# lt8471.net
KiCad netlist of a schematic drawn in EAGLE
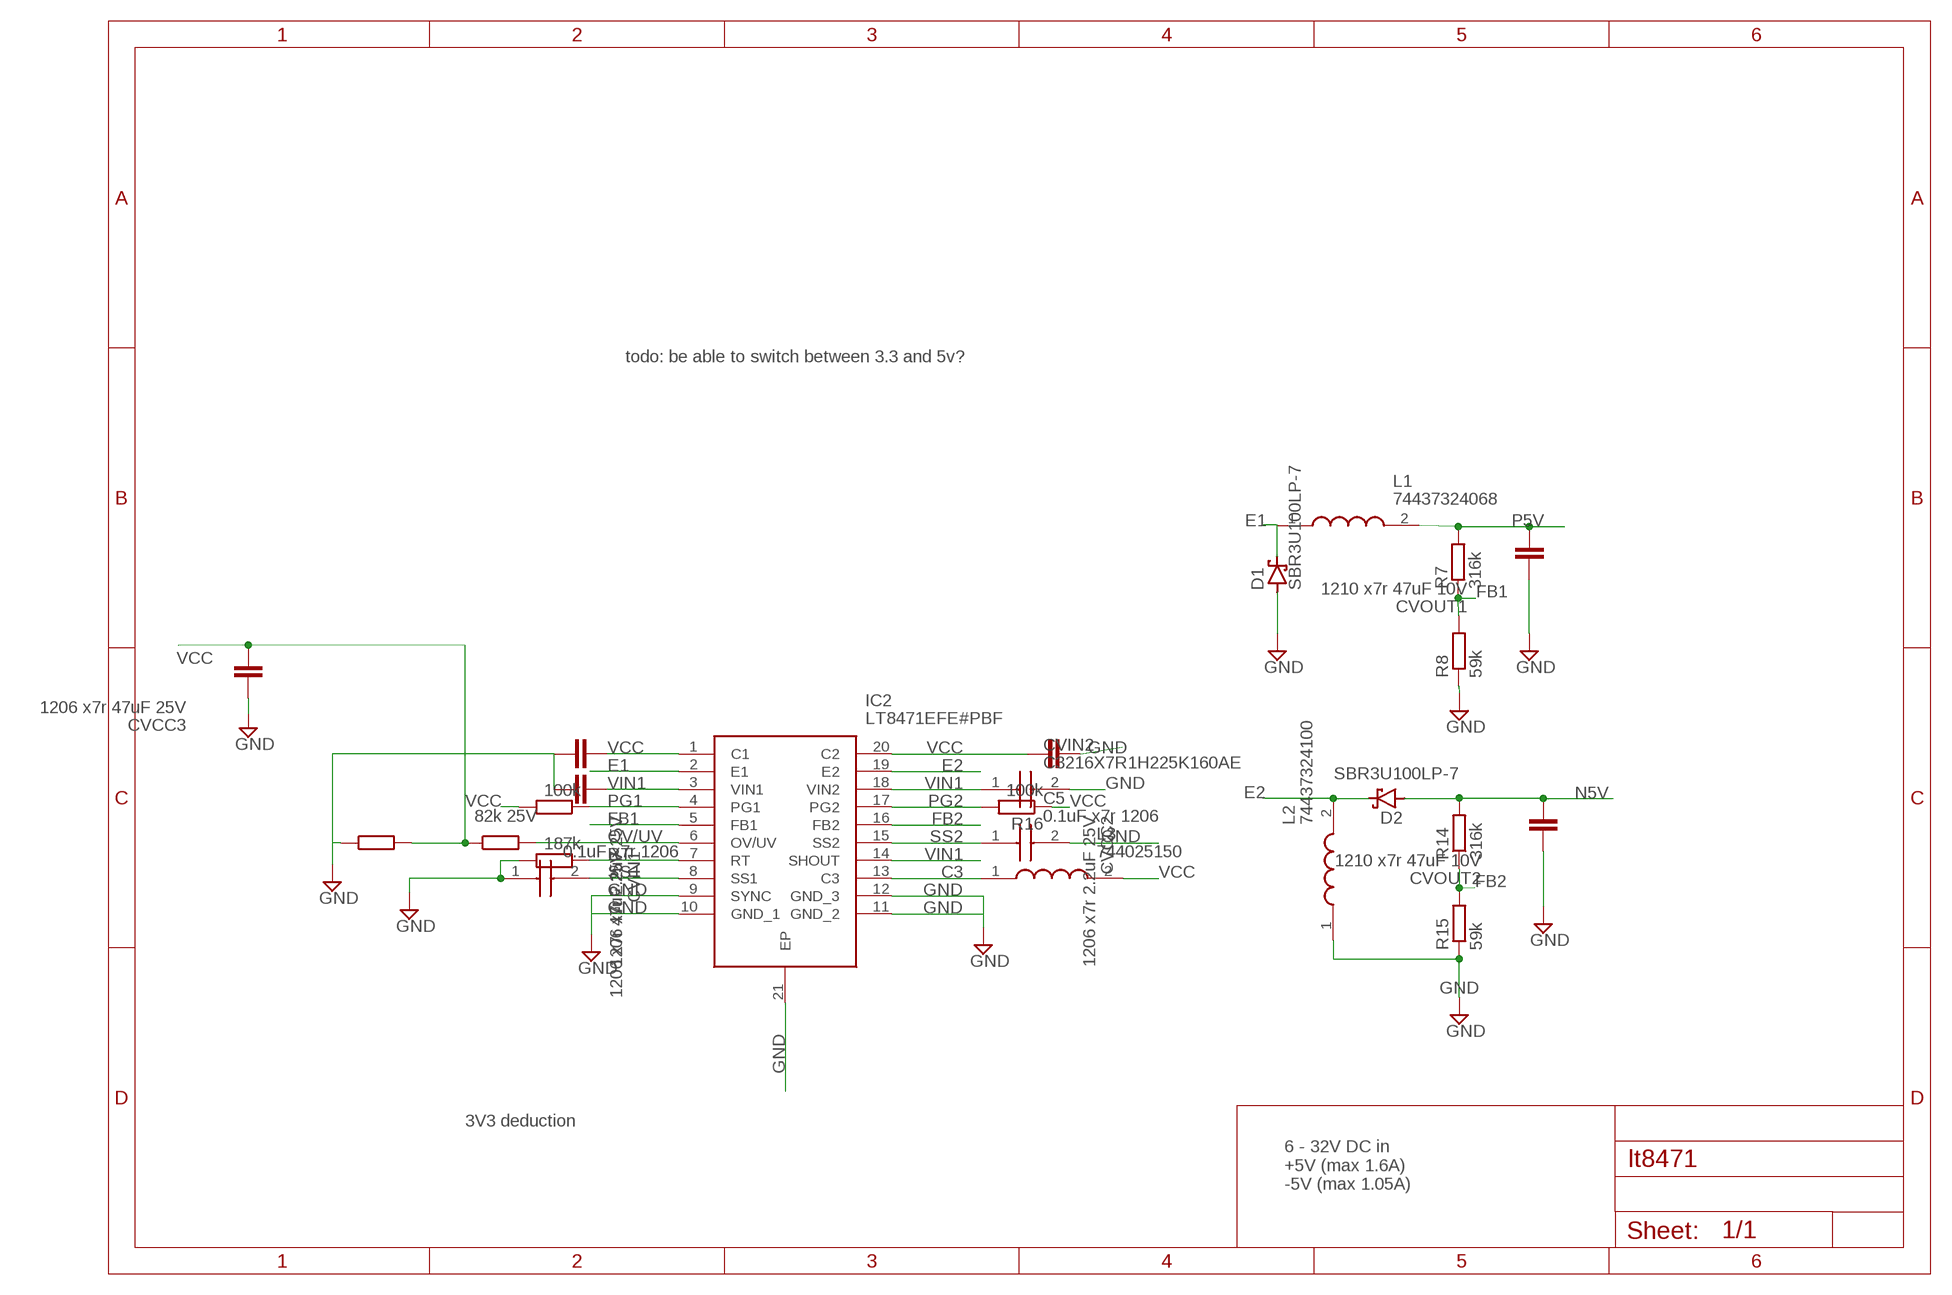
[diagram p0: schematic, sheet 1]

(export (version "E")
  (design (tool "Eeschema 10.0.6"))
  (components
    (comp (ref "C3")
      (value "0.1uF x7r 1206")
      (footprint "eagle-import:CAPC3416X90N")
      (fields (field (name "MANUFACTURER_PART_NUMBER") "MCSH31B104K500CT"))
      (libsource (lib "eagle-import") (part "MCSH31B104K500CT"))
    )
    (comp (ref "C5")
      (value "0.1uF x7r 1206")
      (footprint "eagle-import:CAPC3416X90N")
      (fields (field (name "MANUFACTURER_PART_NUMBER") "MCSH31B104K500CT"))
      (libsource (lib "eagle-import") (part "MCSH31B104K500CT"))
    )
    (comp (ref "CVCC1")
      (value "1206 x7r 2.2uF 25V")
      (footprint "eagle-import:C1206")
      (libsource (lib "eagle-import") (part "C-EUC1206"))
    )
    (comp (ref "CVCC2")
      (value "1206 x7r 2.2uF 25V")
      (footprint "eagle-import:C1206")
      (libsource (lib "eagle-import") (part "C-EUC1206"))
    )
    (comp (ref "CVCC3")
      (value "1206 x7r 47uF 25V")
      (footprint "eagle-import:C1210")
      (libsource (lib "eagle-import") (part "C-EUC1210"))
    )
    (comp (ref "CVIN1")
      (value "1206 x7r 47uF 25V")
      (footprint "eagle-import:C1210")
      (libsource (lib "eagle-import") (part "C-EUC1210"))
    )
    (comp (ref "CVIN2")
      (value "C3216X7R1H225K160AE")
      (footprint "eagle-import:CAPC3216X180N")
      (fields (field (name "MOUSER_PART_NUMBER") "810-C3216X7R1H225KST"))
      (libsource (lib "eagle-import") (part "C3216X7R1H225K160AE"))
    )
    (comp (ref "CVOUT1")
      (value "1210 x7r 47uF 10V")
      (footprint "eagle-import:C1210")
      (libsource (lib "eagle-import") (part "C-EUC1210"))
    )
    (comp (ref "CVOUT2")
      (value "1210 x7r 47uF 10V")
      (footprint "eagle-import:C1210")
      (libsource (lib "eagle-import") (part "C-EUC1210"))
    )
    (comp (ref "D1")
      (value "SBR3U100LP-7")
      (footprint "eagle-import:SBR3U100LP7")
      (fields
        (field (name "MOUSER_PART_NUMBER") "621-SBR3U100LP-7")
        (field (name "RS_PART_NUMBER") "8855599P")
      )
      (libsource (lib "eagle-import") (part "SBR3U100LP-7"))
    )
    (comp (ref "D2")
      (value "SBR3U100LP-7")
      (footprint "eagle-import:SBR3U100LP7")
      (fields
        (field (name "MOUSER_PART_NUMBER") "621-SBR3U100LP-7")
        (field (name "RS_PART_NUMBER") "8855599P")
      )
      (libsource (lib "eagle-import") (part "SBR3U100LP-7"))
    )
    (comp (ref "IC2")
      (value "LT8471EFE#PBF")
      (footprint "eagle-import:SOP65P640X120-21N")
      (fields
        (field (name "MOUSER_PART_NUMBER") "584-LT8471EFE#PBF")
        (field (name "RS_PART_NUMBER") "1513320")
      )
      (libsource (lib "eagle-import") (part "LT8471EFE#PBF"))
    )
    (comp (ref "L1")
      (value "74437324068")
      (footprint "eagle-import:WE-LHMI_402048")
      (fields
        (field (name "MOUSER_PART_NUMBER") "710-74437324068")
        (field (name "RS_PART_NUMBER") "7568480P")
      )
      (libsource (lib "eagle-import") (part "74437324068"))
    )
    (comp (ref "L2")
      (value "74437324100")
      (footprint "eagle-import:WE-LHMI_402048")
      (fields
        (field (name "MOUSER_PART_NUMBER") "710-74437324100")
        (field (name "RS_PART_NUMBER") "7568487P")
      )
      (libsource (lib "eagle-import") (part "74437324100"))
    )
    (comp (ref "L3")
      (value "744025150")
      (footprint "eagle-import:WE-TPC_282892")
      (fields (field (name "MOUSER_PART_NUMBER") "710-744025150") (field (name "RS_PART_NUMBER") "7373639P"))
      (libsource (lib "eagle-import") (part "744025150"))
    )
    (comp (ref "R5")
      (value "261k 25V")
      (footprint "eagle-import:M1206")
      (libsource (lib "eagle-import") (part "resistor_348_R-EU_M1206"))
    )
    (comp (ref "R6")
      (value "82k 25V")
      (footprint "eagle-import:M1206")
      (libsource (lib "eagle-import") (part "resistor_348_R-EU_M1206"))
    )
    (comp (ref "R7")
      (value "316k")
      (footprint "eagle-import:R1206")
      (libsource (lib "eagle-import") (part "R-EU_R1206"))
    )
    (comp (ref "R8")
      (value "59k")
      (footprint "eagle-import:R1206")
      (libsource (lib "eagle-import") (part "R-EU_R1206"))
    )
    (comp (ref "R14")
      (value "316k")
      (footprint "eagle-import:R1206")
      (libsource (lib "eagle-import") (part "R-EU_R1206"))
    )
    (comp (ref "R15")
      (value "59k")
      (footprint "eagle-import:R1206")
      (libsource (lib "eagle-import") (part "R-EU_R1206"))
    )
    (comp (ref "R16")
      (value "100k")
      (footprint "eagle-import:R1206")
      (libsource (lib "eagle-import") (part "R-EU_R1206"))
    )
    (comp (ref "R17")
      (value "100k")
      (footprint "eagle-import:R1206")
      (libsource (lib "eagle-import") (part "R-EU_R1206"))
    )
    (comp (ref "R18")
      (value "187k")
      (footprint "eagle-import:R1206")
      (libsource (lib "eagle-import") (part "R-EU_R1206"))
    )
  )
  (nets
    (net (code "1") (name "/C3") (class "Default")
      (node (ref "IC2") (pin "13") (pinfunction "C3_13") (pintype "bidirectional"))
      (node (ref "L3") (pin "1") (pinfunction "1_1") (pintype "bidirectional"))
    )
    (net (code "2") (name "/E1") (class "Default")
      (node (ref "D1") (pin "5") (pinfunction "C_5") (pintype "passive"))
      (node (ref "IC2") (pin "2") (pinfunction "E1_2") (pintype "bidirectional"))
      (node (ref "L1") (pin "1") (pinfunction "1_1") (pintype "bidirectional"))
    )
    (net (code "3") (name "/E2") (class "Default")
      (node (ref "D2") (pin "5") (pinfunction "C_5") (pintype "passive"))
      (node (ref "IC2") (pin "19") (pinfunction "E2_19") (pintype "bidirectional"))
      (node (ref "L2") (pin "2") (pinfunction "2_2") (pintype "bidirectional"))
    )
    (net (code "4") (name "/FB1") (class "Default")
      (node (ref "IC2") (pin "5") (pinfunction "FB1_5") (pintype "bidirectional"))
      (node (ref "R7") (pin "1") (pinfunction "1_1") (pintype "passive"))
      (node (ref "R8") (pin "2") (pinfunction "2_2") (pintype "passive"))
    )
    (net (code "5") (name "/FB2") (class "Default")
      (node (ref "IC2") (pin "16") (pinfunction "FB2_16") (pintype "bidirectional"))
      (node (ref "R14") (pin "1") (pinfunction "1_1") (pintype "passive"))
      (node (ref "R15") (pin "2") (pinfunction "2_2") (pintype "passive"))
    )
    (net (code "6") (name "/N5V") (class "Default")
      (node (ref "CVOUT2") (pin "2") (pinfunction "2_2") (pintype "passive"))
      (node (ref "D2") (pin "1") (pinfunction "A_1") (pintype "passive"))
      (node (ref "D2") (pin "2") (pinfunction "A_2") (pintype "passive"))
      (node (ref "D2") (pin "3") (pinfunction "A_3") (pintype "passive"))
      (node (ref "D2") (pin "4") (pinfunction "A_4") (pintype "passive"))
      (node (ref "R14") (pin "2") (pinfunction "2_2") (pintype "passive"))
    )
    (net (code "7") (name "/OV{slash}UV") (class "Default")
      (node (ref "IC2") (pin "6") (pinfunction "OV/UV_6") (pintype "bidirectional"))
      (node (ref "R5") (pin "2") (pinfunction "2_2") (pintype "passive"))
    )
    (net (code "8") (name "/P5V") (class "Default")
      (node (ref "CVOUT1") (pin "2") (pinfunction "2_2") (pintype "passive"))
      (node (ref "L1") (pin "2") (pinfunction "2_2") (pintype "bidirectional"))
      (node (ref "R7") (pin "2") (pinfunction "2_2") (pintype "passive"))
    )
    (net (code "9") (name "/PG1") (class "Default")
      (node (ref "IC2") (pin "4") (pinfunction "PG1_4") (pintype "bidirectional"))
      (node (ref "R17") (pin "1") (pinfunction "1_1") (pintype "passive"))
    )
    (net (code "10") (name "/PG2") (class "Default")
      (node (ref "IC2") (pin "17") (pinfunction "PG2_17") (pintype "bidirectional"))
      (node (ref "R16") (pin "2") (pinfunction "2_2") (pintype "passive"))
    )
    (net (code "11") (name "/RT") (class "Default")
      (node (ref "IC2") (pin "7") (pinfunction "RT_7") (pintype "bidirectional"))
      (node (ref "R18") (pin "1") (pinfunction "1_1") (pintype "passive"))
    )
    (net (code "12") (name "/SS1") (class "Default")
      (node (ref "C3") (pin "2") (pinfunction "2_2") (pintype "bidirectional"))
      (node (ref "IC2") (pin "8") (pinfunction "SS1_8") (pintype "bidirectional"))
    )
    (net (code "13") (name "/SS2") (class "Default")
      (node (ref "C5") (pin "1") (pinfunction "1_1") (pintype "bidirectional"))
      (node (ref "IC2") (pin "15") (pinfunction "SS2_15") (pintype "bidirectional"))
    )
    (net (code "14") (name "/VCC") (class "Default")
      (node (ref "CVCC1") (pin "1") (pinfunction "1_1") (pintype "passive"))
      (node (ref "CVCC2") (pin "2") (pinfunction "2_2") (pintype "passive"))
      (node (ref "CVCC3") (pin "2") (pinfunction "2_2") (pintype "passive"))
      (node (ref "IC2") (pin "1") (pinfunction "C1_1") (pintype "bidirectional"))
      (node (ref "IC2") (pin "20") (pinfunction "C2_20") (pintype "bidirectional"))
      (node (ref "L3") (pin "2") (pinfunction "2_2") (pintype "bidirectional"))
      (node (ref "R16") (pin "1") (pinfunction "1_1") (pintype "passive"))
      (node (ref "R17") (pin "2") (pinfunction "2_2") (pintype "passive"))
      (node (ref "R5") (pin "1") (pinfunction "1_1") (pintype "passive"))
      (node (ref "R6") (pin "2") (pinfunction "2_2") (pintype "passive"))
    )
    (net (code "15") (name "/VIN1") (class "Default")
      (node (ref "CVIN1") (pin "1") (pinfunction "1_1") (pintype "passive"))
      (node (ref "CVIN2") (pin "1") (pinfunction "1_1") (pintype "bidirectional"))
      (node (ref "IC2") (pin "14") (pinfunction "SHOUT_14") (pintype "bidirectional"))
      (node (ref "IC2") (pin "18") (pinfunction "VIN2_18") (pintype "bidirectional"))
      (node (ref "IC2") (pin "3") (pinfunction "VIN1_3") (pintype "bidirectional"))
    )
    (net (code "16") (name "GND") (class "Default")
      (node (ref "C3") (pin "1") (pinfunction "1_1") (pintype "bidirectional"))
      (node (ref "C5") (pin "2") (pinfunction "2_2") (pintype "bidirectional"))
      (node (ref "CVCC1") (pin "2") (pinfunction "2_2") (pintype "passive"))
      (node (ref "CVCC2") (pin "1") (pinfunction "1_1") (pintype "passive"))
      (node (ref "CVCC3") (pin "1") (pinfunction "1_1") (pintype "passive"))
      (node (ref "CVIN1") (pin "2") (pinfunction "2_2") (pintype "passive"))
      (node (ref "CVIN2") (pin "2") (pinfunction "2_2") (pintype "bidirectional"))
      (node (ref "CVOUT1") (pin "1") (pinfunction "1_1") (pintype "passive"))
      (node (ref "CVOUT2") (pin "1") (pinfunction "1_1") (pintype "passive"))
      (node (ref "D1") (pin "1") (pinfunction "A_1") (pintype "passive"))
      (node (ref "D1") (pin "2") (pinfunction "A_2") (pintype "passive"))
      (node (ref "D1") (pin "3") (pinfunction "A_3") (pintype "passive"))
      (node (ref "D1") (pin "4") (pinfunction "A_4") (pintype "passive"))
      (node (ref "IC2") (pin "10") (pinfunction "GND_1_10") (pintype "bidirectional"))
      (node (ref "IC2") (pin "11") (pinfunction "GND_2_11") (pintype "bidirectional"))
      (node (ref "IC2") (pin "12") (pinfunction "GND_3_12") (pintype "bidirectional"))
      (node (ref "IC2") (pin "21") (pinfunction "EP_21") (pintype "bidirectional"))
      (node (ref "IC2") (pin "9") (pinfunction "SYNC_9") (pintype "bidirectional"))
      (node (ref "L2") (pin "1") (pinfunction "1_1") (pintype "bidirectional"))
      (node (ref "R15") (pin "1") (pinfunction "1_1") (pintype "passive"))
      (node (ref "R18") (pin "2") (pinfunction "2_2") (pintype "passive"))
      (node (ref "R6") (pin "1") (pinfunction "1_1") (pintype "passive"))
      (node (ref "R8") (pin "1") (pinfunction "1_1") (pintype "passive"))
    )
  )
)
